# Sheet3.net
KiCad netlist of a schematic drawn in Altium Designer
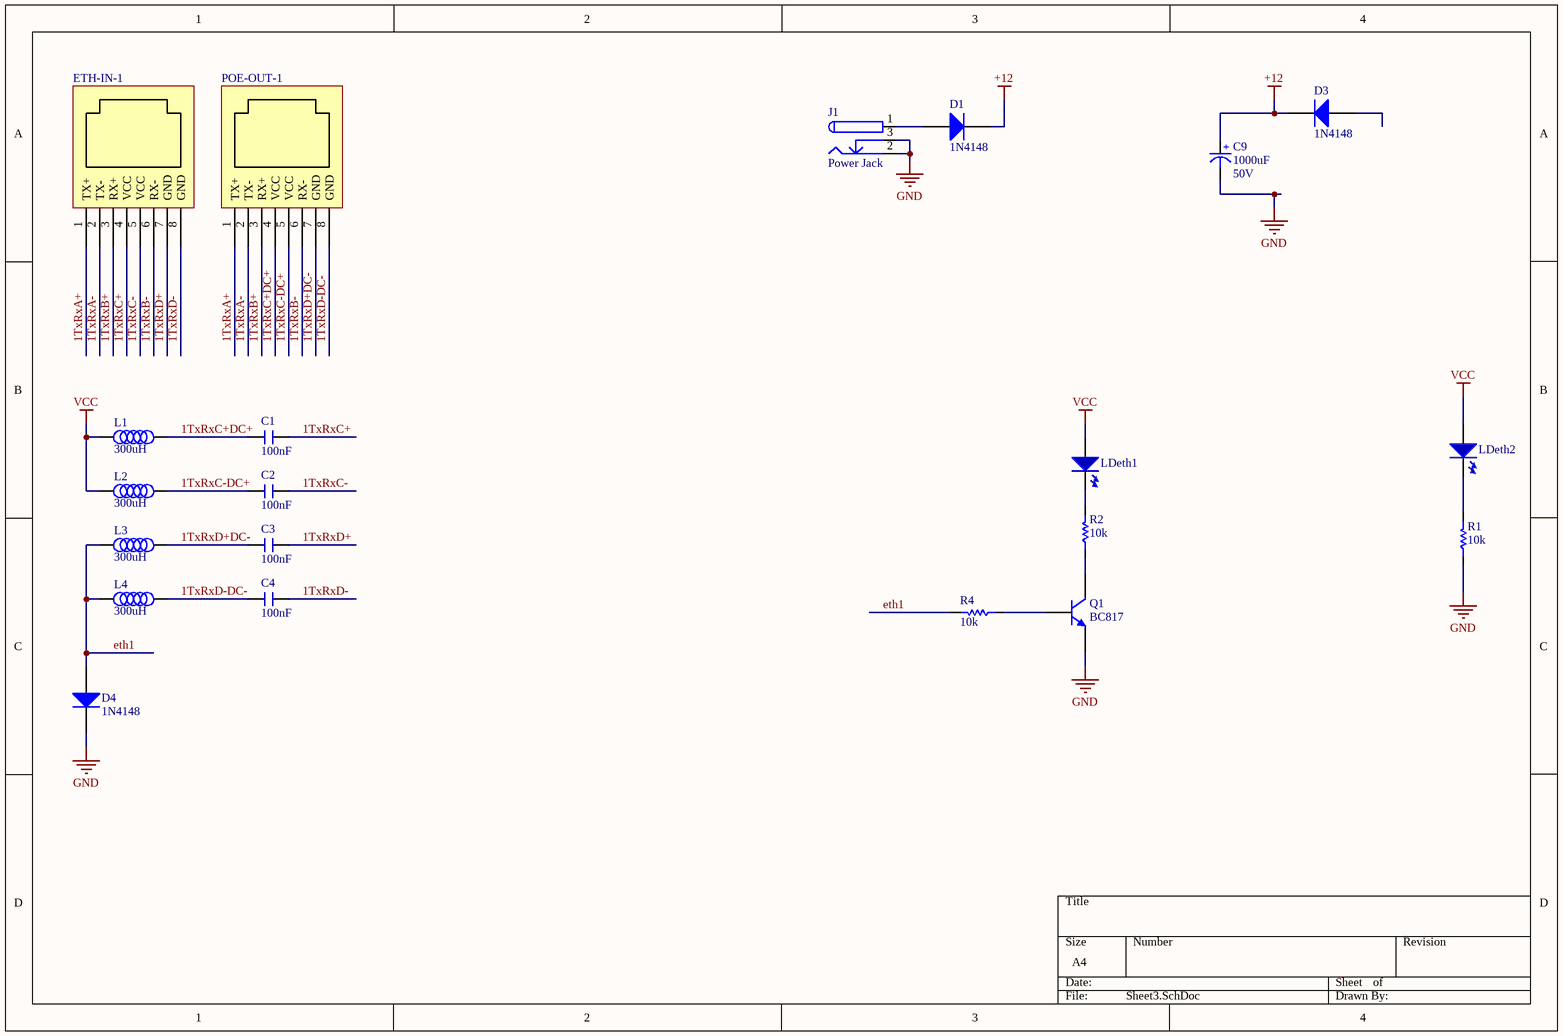
[diagram p0: Sheet3.SchDoc]

(export (version "E")
  (design (tool "Eeschema 10.0.6"))
  (components
    (comp (ref "C1")
      (value "Capacitor SMD")
      (footprint "1206 Capacitor")
      (fields (field (name "ALTIUM_UNNAMED_1") "100nF"))
      (libsource (lib "ZetaBoard_Lib") (part "Capacitor SMD"))
    )
    (comp (ref "C2")
      (value "Capacitor SMD")
      (footprint "1206 Capacitor")
      (fields (field (name "ALTIUM_UNNAMED_1") "100nF"))
      (libsource (lib "ZetaBoard_Lib") (part "Capacitor SMD"))
    )
    (comp (ref "C3")
      (value "Capacitor SMD")
      (footprint "1206 Capacitor")
      (fields (field (name "ALTIUM_UNNAMED_1") "100nF"))
      (libsource (lib "ZetaBoard_Lib") (part "Capacitor SMD"))
    )
    (comp (ref "C4")
      (value "Capacitor SMD")
      (footprint "1206 Capacitor")
      (fields (field (name "ALTIUM_UNNAMED_1") "100nF"))
      (libsource (lib "ZetaBoard_Lib") (part "Capacitor SMD"))
    )
    (comp (ref "C9")
      (value "1000uF")
      (footprint "CAP 05")
      (description "Polar Capacitor")
      (fields (field (name "VOLTAGE") "50V") (field (name "DESIGNER") "Saeid Jorablo"))
      (libsource (lib "Electrovolt Lib") (part "Cap-Polar"))
    )
    (comp (ref "D1")
      (value "1N4148")
      (footprint "LL4148")
      (description "High Conductance Fast Diode")
      (fields (field (name "PUBLISHER") "Altium Limited"))
      (libsource (lib "Electrovolt Lib") (part "Diode 1N4148"))
    )
    (comp (ref "D3")
      (value "1N4148")
      (footprint "LL4148")
      (description "High Conductance Fast Diode")
      (fields (field (name "PUBLISHER") "Altium Limited"))
      (libsource (lib "Electrovolt Lib") (part "Diode 1N4148"))
    )
    (comp (ref "D4")
      (value "1N4148")
      (footprint "LL4148")
      (description "High Conductance Fast Diode")
      (fields (field (name "PUBLISHER") "Altium Limited"))
      (libsource (lib "Electrovolt Lib") (part "Diode 1N4148"))
    )
    (comp (ref "ETH-IN-1")
      (value "RJ45-w57-1")
      (footprint "rj45-hb")
      (libsource (lib "Schlib1") (part "RJ45-w57-1"))
    )
    (comp (ref "J1")
      (value "Power Jack")
      (footprint "Power Jack")
      (fields (field (name "DESIGNER") "Saeid Jorablo"))
      (libsource (lib "Electrovolt Lib") (part "Power Jack"))
    )
    (comp (ref "L1")
      (value "300uH")
      (footprint "inductor")
      (libsource (lib "ZetaBoard_Lib") (part "Inductor SMT"))
    )
    (comp (ref "L2")
      (value "300uH")
      (footprint "inductor")
      (libsource (lib "ZetaBoard_Lib") (part "Inductor SMT"))
    )
    (comp (ref "L3")
      (value "300uH")
      (footprint "inductor")
      (libsource (lib "ZetaBoard_Lib") (part "Inductor SMT"))
    )
    (comp (ref "L4")
      (value "300uH")
      (footprint "inductor")
      (libsource (lib "ZetaBoard_Lib") (part "Inductor SMT"))
    )
    (comp (ref "LDeth1")
      (value "SMD LED")
      (footprint "LED 1 X  3mm GREEN RIGHT ANGLE")
      (libsource (lib "ZetaBoard_Lib") (part "LED SMD"))
    )
    (comp (ref "LDeth2")
      (value "SMD LED")
      (footprint "LED 1 X  3mm GREEN RIGHT ANGLE")
      (libsource (lib "ZetaBoard_Lib") (part "LED SMD"))
    )
    (comp (ref "POE-OUT-1")
      (value "RJ45-w57-1")
      (footprint "rj45-hb")
      (libsource (lib "Schlib1") (part "RJ45-w57-1"))
    )
    (comp (ref "Q1") (value "BC817") (footprint "SOT-23") (libsource (lib "ZetaBoard_Lib") (part "BC817")))
    (comp (ref "R1")
      (value "10k")
      (footprint "RES 1206 (3216X08L)")
      (description "Resistor")
      (fields (field (name "TOLERANCE") "5%") (field (name "POWER") "1/8 W"))
      (libsource (lib "Electrovolt Lib") (part "Resistor"))
    )
    (comp (ref "R2")
      (value "10k")
      (footprint "RES 1206 (3216X08L)")
      (description "Resistor")
      (fields (field (name "TOLERANCE") "5%") (field (name "POWER") "1/8 W"))
      (libsource (lib "Electrovolt Lib") (part "Resistor"))
    )
    (comp (ref "R4")
      (value "10k")
      (footprint "RES 1206 (3216X08L)")
      (description "Resistor")
      (fields (field (name "TOLERANCE") "5%") (field (name "POWER") "1/8 W"))
      (libsource (lib "Electrovolt Lib") (part "Resistor"))
    )
  )
  (nets
    (net (code "1") (name "+12") (class "Default")
      (node (ref "C9") (pin "1") (pinfunction "+_1") (pintype "passive"))
      (node (ref "D1") (pin "2") (pinfunction "K_2") (pintype "passive"))
      (node (ref "D3") (pin "2") (pinfunction "K_2") (pintype "passive"))
    )
    (net (code "2") (name "/1TxRxA+") (class "Default")
      (node (ref "ETH-IN-1") (pin "1") (pinfunction "TX+_1") (pintype "passive"))
      (node (ref "POE-OUT-1") (pin "1") (pinfunction "TX+_1") (pintype "passive"))
    )
    (net (code "3") (name "/1TxRxA-") (class "Default")
      (node (ref "ETH-IN-1") (pin "2") (pinfunction "TX-_2") (pintype "passive"))
      (node (ref "POE-OUT-1") (pin "2") (pinfunction "TX-_2") (pintype "passive"))
    )
    (net (code "4") (name "/1TxRxB+") (class "Default")
      (node (ref "ETH-IN-1") (pin "3") (pinfunction "RX+_3") (pintype "passive"))
      (node (ref "POE-OUT-1") (pin "3") (pinfunction "RX+_3") (pintype "passive"))
    )
    (net (code "5") (name "/1TxRxB-") (class "Default")
      (node (ref "ETH-IN-1") (pin "6") (pinfunction "RX-_6") (pintype "passive"))
      (node (ref "POE-OUT-1") (pin "6") (pinfunction "RX-_6") (pintype "passive"))
    )
    (net (code "6") (name "/1TxRxC+") (class "Default")
      (node (ref "C1") (pin "2") (pintype "passive"))
      (node (ref "ETH-IN-1") (pin "4") (pinfunction "VCC_4") (pintype "passive"))
    )
    (net (code "7") (name "/1TxRxC+DC+") (class "Default")
      (node (ref "C1") (pin "1") (pintype "passive"))
      (node (ref "L1") (pin "2") (pintype "passive"))
      (node (ref "POE-OUT-1") (pin "4") (pinfunction "VCC_4") (pintype "passive"))
    )
    (net (code "8") (name "/1TxRxC-") (class "Default")
      (node (ref "C2") (pin "2") (pintype "passive"))
      (node (ref "ETH-IN-1") (pin "5") (pinfunction "VCC_5") (pintype "passive"))
    )
    (net (code "9") (name "/1TxRxC-DC+") (class "Default")
      (node (ref "C2") (pin "1") (pintype "passive"))
      (node (ref "L2") (pin "2") (pintype "passive"))
      (node (ref "POE-OUT-1") (pin "5") (pinfunction "VCC_5") (pintype "passive"))
    )
    (net (code "10") (name "/1TxRxD+") (class "Default")
      (node (ref "C3") (pin "2") (pintype "passive"))
      (node (ref "ETH-IN-1") (pin "7") (pinfunction "GND_7") (pintype "passive"))
    )
    (net (code "11") (name "/1TxRxD+DC-") (class "Default")
      (node (ref "C3") (pin "1") (pintype "passive"))
      (node (ref "L3") (pin "2") (pintype "passive"))
      (node (ref "POE-OUT-1") (pin "7") (pinfunction "GND_7") (pintype "passive"))
    )
    (net (code "12") (name "/1TxRxD-") (class "Default")
      (node (ref "C4") (pin "2") (pintype "passive"))
      (node (ref "ETH-IN-1") (pin "8") (pinfunction "GND_8") (pintype "passive"))
    )
    (net (code "13") (name "/1TxRxD-DC-") (class "Default")
      (node (ref "C4") (pin "1") (pintype "passive"))
      (node (ref "L4") (pin "2") (pintype "passive"))
      (node (ref "POE-OUT-1") (pin "8") (pinfunction "GND_8") (pintype "passive"))
    )
    (net (code "14") (name "/eth1") (class "Default")
      (node (ref "D4") (pin "1") (pinfunction "A_1") (pintype "passive"))
      (node (ref "L3") (pin "1") (pintype "passive"))
      (node (ref "L4") (pin "1") (pintype "passive"))
      (node (ref "R4") (pin "2") (pinfunction "2_2") (pintype "passive"))
    )
    (net (code "15") (name "GND") (class "Default")
      (node (ref "C9") (pin "2") (pinfunction "-_2") (pintype "passive"))
      (node (ref "D4") (pin "2") (pinfunction "K_2") (pintype "passive"))
      (node (ref "J1") (pin "2") (pinfunction "2_2") (pintype "power_in"))
      (node (ref "J1") (pin "3") (pinfunction "3_3") (pintype "power_in"))
      (node (ref "Q1") (pin "2") (pinfunction "E_2") (pintype "passive"))
      (node (ref "R1") (pin "1") (pinfunction "1_1") (pintype "passive"))
    )
    (net (code "16") (name "Net-(D1-A)") (class "Default")
      (node (ref "D1") (pin "1") (pinfunction "A_1") (pintype "passive"))
      (node (ref "J1") (pin "1") (pinfunction "1_1") (pintype "power_in"))
    )
    (net (code "17") (name "Net-(LDeth1-K)") (class "Default")
      (node (ref "LDeth1") (pin "2") (pinfunction "K_2") (pintype "passive"))
      (node (ref "R2") (pin "2") (pinfunction "2_2") (pintype "passive"))
    )
    (net (code "18") (name "Net-(LDeth2-K)") (class "Default")
      (node (ref "LDeth2") (pin "2") (pinfunction "K_2") (pintype "passive"))
      (node (ref "R1") (pin "2") (pinfunction "2_2") (pintype "passive"))
    )
    (net (code "19") (name "Net-(Q1-B)") (class "Default")
      (node (ref "Q1") (pin "1") (pinfunction "B_1") (pintype "passive"))
      (node (ref "R4") (pin "1") (pinfunction "1_1") (pintype "passive"))
    )
    (net (code "20") (name "Net-(Q1-C)") (class "Default")
      (node (ref "Q1") (pin "3") (pinfunction "C_3") (pintype "passive"))
      (node (ref "R2") (pin "1") (pinfunction "1_1") (pintype "passive"))
    )
    (net (code "21") (name "VCC") (class "Default")
      (node (ref "L1") (pin "1") (pintype "passive"))
      (node (ref "L2") (pin "1") (pintype "passive"))
      (node (ref "LDeth1") (pin "1") (pinfunction "A_1") (pintype "passive"))
      (node (ref "LDeth2") (pin "1") (pinfunction "A_1") (pintype "passive"))
    )
    (net (code "22") (name "unconnected-(D3-A-Pad1)") (class "Default")
      (node (ref "D3") (pin "1") (pinfunction "A_1") (pintype "passive"))
    )
  )
)
